# Control.net
KiCad netlist of a schematic drawn in Altium Designer
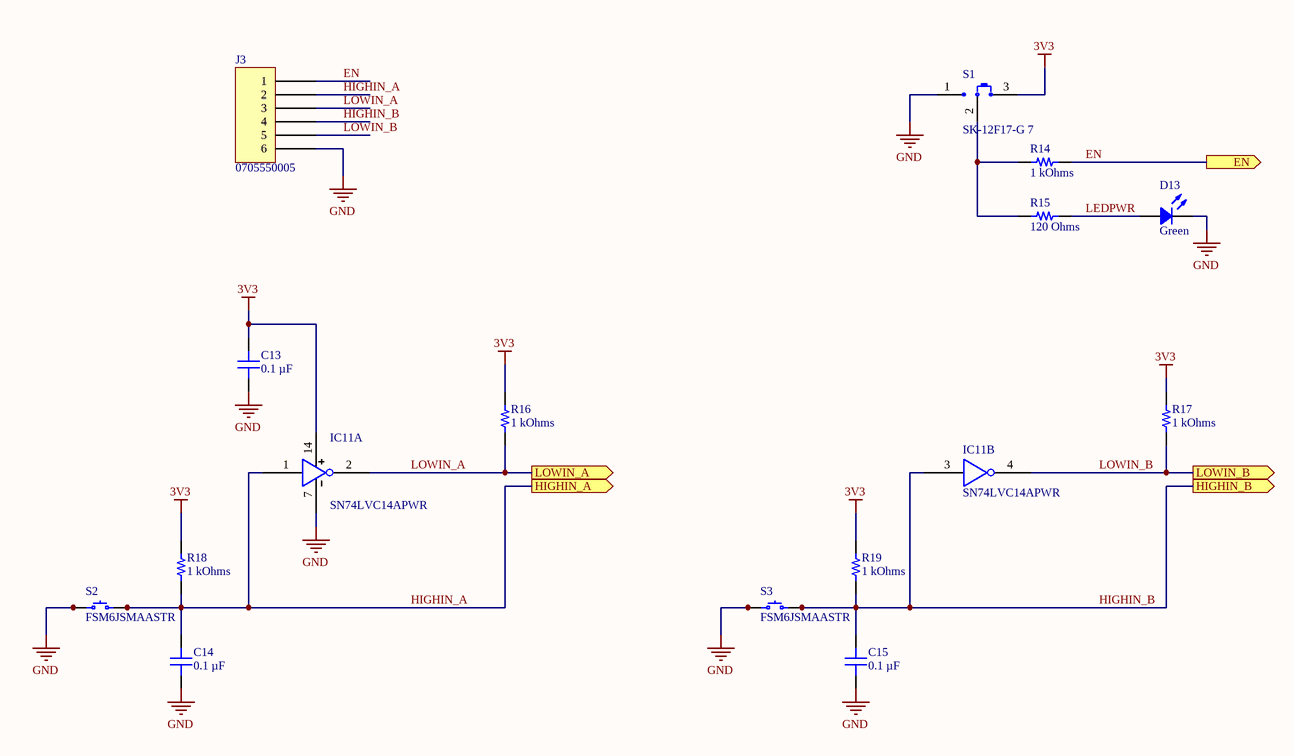
[diagram p0: Control.SchDoc]

(export (version "E")
  (design (tool "Eeschema 10.0.6"))
  (components
    (comp (ref "C13")
      (value "0.1 µF")
      (footprint "CAP 0603_1608")
      (description "CAP CER 0.1UF 10V X7R 0603")
      (fields (field (name "PART NUMBER") "C0603C104K8RAC7867") (field (name "MANUFACTURER") "KEMET"))
      (libsource (lib "altiumlibrary.com") (part "Capacitor"))
    )
    (comp (ref "C14")
      (value "0.1 µF")
      (footprint "CAP 0603_1608")
      (description "CAP CER 0.1UF 10V X7R 0603")
      (fields (field (name "PART NUMBER") "C0603C104K8RAC7867") (field (name "MANUFACTURER") "KEMET"))
      (libsource (lib "altiumlibrary.com") (part "Capacitor"))
    )
    (comp (ref "C15")
      (value "0.1 µF")
      (footprint "CAP 0603_1608")
      (description "CAP CER 0.1UF 10V X7R 0603")
      (fields (field (name "PART NUMBER") "C0603C104K8RAC7867") (field (name "MANUFACTURER") "KEMET"))
      (libsource (lib "altiumlibrary.com") (part "Capacitor"))
    )
    (comp (ref "D13")
      (value "Green")
      (footprint "LED 0603_1608 GREEN")
      (description "LED GREEN CLEAR CHIP SMD")
      (fields (field (name "PART NUMBER") "XZMG53W-1") (field (name "MANUFACTURER") "SunLED"))
      (libsource (lib "altiumlibrary.com") (part "LED"))
    )
    (comp (ref "IC11")
      (value "SN74LVC14APWR")
      (footprint "TI TSSOP-14 PW")
      (description "IC INVERTER 6CH 6-INP 14TSSOP")
      (fields (field (name "MANUFACTURER") "Texas Instruments"))
      (libsource (lib "altiumlibrary.com") (part "TI SNx4LVC14A DIL"))
    )
    (comp (ref "J3")
      (value "0705550005")
      (footprint "MOLEX SDA-70555-6PIN")
      (description "CONN HEADER R/A 6POS 2.54MM")
      (fields (field (name "MANUFACTURER") "Molex"))
      (libsource (lib "altiumlibrary.com") (part "6 Pin"))
    )
    (comp (ref "R14")
      (value "1 kOhms")
      (footprint "RES 0603_1608")
      (description "RES SMD 1K OHM 5% 1/4W 0603")
      (fields
        (field (name "PART NUMBER") "ERJ-PA3J102V")
        (field (name "MANUFACTURER") "Panasonic Electronic Components")
      )
      (libsource (lib "altiumlibrary.com") (part "Resistor"))
    )
    (comp (ref "R15")
      (value "120 Ohms")
      (footprint "RES 0603_1608")
      (description "RES SMD 120 OHM 5% 1/4W 0603")
      (fields
        (field (name "PART NUMBER") "ERJ-PA3J121V")
        (field (name "MANUFACTURER") "Panasonic Electronic Components")
      )
      (libsource (lib "altiumlibrary.com") (part "Resistor"))
    )
    (comp (ref "R16")
      (value "1 kOhms")
      (footprint "RES 0603_1608")
      (description "RES SMD 1K OHM 5% 1/4W 0603")
      (fields
        (field (name "PART NUMBER") "ERJ-PA3J102V")
        (field (name "MANUFACTURER") "Panasonic Electronic Components")
      )
      (libsource (lib "altiumlibrary.com") (part "Resistor"))
    )
    (comp (ref "R17")
      (value "1 kOhms")
      (footprint "RES 0603_1608")
      (description "RES SMD 1K OHM 5% 1/4W 0603")
      (fields
        (field (name "PART NUMBER") "ERJ-PA3J102V")
        (field (name "MANUFACTURER") "Panasonic Electronic Components")
      )
      (libsource (lib "altiumlibrary.com") (part "Resistor"))
    )
    (comp (ref "R18")
      (value "1 kOhms")
      (footprint "RES 0603_1608")
      (description "RES SMD 1K OHM 5% 1/4W 0603")
      (fields
        (field (name "PART NUMBER") "ERJ-PA3J102V")
        (field (name "MANUFACTURER") "Panasonic Electronic Components")
      )
      (libsource (lib "altiumlibrary.com") (part "Resistor"))
    )
    (comp (ref "R19")
      (value "1 kOhms")
      (footprint "RES 0603_1608")
      (description "RES SMD 1K OHM 5% 1/4W 0603")
      (fields
        (field (name "PART NUMBER") "ERJ-PA3J102V")
        (field (name "MANUFACTURER") "Panasonic Electronic Components")
      )
      (libsource (lib "altiumlibrary.com") (part "Resistor"))
    )
    (comp (ref "S1")
      (value "SK-12F17-G 7")
      (footprint "C&K SK-12F17-G 7")
      (description "SWITCH SLIDE SPDT 300MA 30V")
      (fields (field (name "MANUFACTURER") "C&K"))
      (libsource (lib "altiumlibrary.com") (part "C&K SK-12F17-G 7"))
    )
    (comp (ref "S2")
      (value "FSM6JSMAASTR")
      (footprint "TE FSM6JSMA")
      (description "SWITCH TACTILE SPST-NO 0.05A 24V")
      (fields (field (name "MANUFACTURER") "TE Connectivity ALCOSWITCH Switches"))
      (libsource (lib "altiumlibrary.com") (part "SPST-NO 4 PIN"))
    )
    (comp (ref "S3")
      (value "FSM6JSMAASTR")
      (footprint "TE FSM6JSMA")
      (description "SWITCH TACTILE SPST-NO 0.05A 24V")
      (fields (field (name "MANUFACTURER") "TE Connectivity ALCOSWITCH Switches"))
      (libsource (lib "altiumlibrary.com") (part "SPST-NO 4 PIN"))
    )
  )
  (nets
    (net (code "1") (name "/EN") (class "Default")
      (node (ref "J3") (pin "1") (pinfunction "1_1") (pintype "passive"))
      (node (ref "R14") (pin "2") (pinfunction "2_2") (pintype "passive"))
    )
    (net (code "2") (name "/HIGHIN_A") (class "Default")
      (node (ref "C14") (pin "2") (pinfunction "2_2") (pintype "passive"))
      (node (ref "IC11") (pin "1") (pinfunction "1A_1") (pintype "passive"))
      (node (ref "J3") (pin "2") (pinfunction "2_2") (pintype "passive"))
      (node (ref "R18") (pin "1") (pinfunction "1_1") (pintype "passive"))
      (node (ref "S2") (pin "3") (pinfunction "3_3") (pintype "passive"))
      (node (ref "S2") (pin "4") (pinfunction "4_4") (pintype "passive"))
    )
    (net (code "3") (name "/HIGHIN_B") (class "Default")
      (node (ref "C15") (pin "2") (pinfunction "2_2") (pintype "passive"))
      (node (ref "IC11") (pin "3") (pinfunction "2A_3") (pintype "passive"))
      (node (ref "J3") (pin "4") (pinfunction "4_4") (pintype "passive"))
      (node (ref "R19") (pin "1") (pinfunction "1_1") (pintype "passive"))
      (node (ref "S3") (pin "3") (pinfunction "3_3") (pintype "passive"))
      (node (ref "S3") (pin "4") (pinfunction "4_4") (pintype "passive"))
    )
    (net (code "4") (name "/LEDPWR") (class "Default")
      (node (ref "D13") (pin "1") (pinfunction "1_1") (pintype "passive"))
      (node (ref "R15") (pin "2") (pinfunction "2_2") (pintype "passive"))
    )
    (net (code "5") (name "/LOWIN_A") (class "Default")
      (node (ref "IC11") (pin "2") (pinfunction "1Y_2") (pintype "passive"))
      (node (ref "J3") (pin "3") (pinfunction "3_3") (pintype "passive"))
      (node (ref "R16") (pin "1") (pinfunction "1_1") (pintype "passive"))
    )
    (net (code "6") (name "/LOWIN_B") (class "Default")
      (node (ref "IC11") (pin "4") (pinfunction "2Y_4") (pintype "passive"))
      (node (ref "J3") (pin "5") (pinfunction "5_5") (pintype "passive"))
      (node (ref "R17") (pin "1") (pinfunction "1_1") (pintype "passive"))
    )
    (net (code "7") (name "3V3") (class "Default")
      (node (ref "C13") (pin "2") (pinfunction "2_2") (pintype "passive"))
      (node (ref "IC11") (pin "14") (pinfunction "VCC_14") (pintype "passive"))
      (node (ref "R16") (pin "2") (pinfunction "2_2") (pintype "passive"))
      (node (ref "R17") (pin "2") (pinfunction "2_2") (pintype "passive"))
      (node (ref "R18") (pin "2") (pinfunction "2_2") (pintype "passive"))
      (node (ref "R19") (pin "2") (pinfunction "2_2") (pintype "passive"))
      (node (ref "S1") (pin "3") (pinfunction "3_3") (pintype "passive"))
    )
    (net (code "8") (name "GND") (class "Default")
      (node (ref "C13") (pin "1") (pinfunction "1_1") (pintype "passive"))
      (node (ref "C14") (pin "1") (pinfunction "1_1") (pintype "passive"))
      (node (ref "C15") (pin "1") (pinfunction "1_1") (pintype "passive"))
      (node (ref "D13") (pin "2") (pinfunction "2_2") (pintype "passive"))
      (node (ref "IC11") (pin "7") (pinfunction "GND_7") (pintype "passive"))
      (node (ref "J3") (pin "6") (pinfunction "6_6") (pintype "passive"))
      (node (ref "S1") (pin "1") (pinfunction "1_1") (pintype "passive"))
      (node (ref "S2") (pin "1") (pinfunction "1_1") (pintype "passive"))
      (node (ref "S2") (pin "2") (pinfunction "2_2") (pintype "passive"))
      (node (ref "S3") (pin "1") (pinfunction "1_1") (pintype "passive"))
      (node (ref "S3") (pin "2") (pinfunction "2_2") (pintype "passive"))
    )
    (net (code "9") (name "Net-(S1-COM)") (class "Default")
      (node (ref "R14") (pin "1") (pinfunction "1_1") (pintype "passive"))
      (node (ref "R15") (pin "1") (pinfunction "1_1") (pintype "passive"))
      (node (ref "S1") (pin "2") (pinfunction "COM_2") (pintype "passive"))
    )
  )
)
